# Ekran.net
KiCad netlist of a schematic drawn in EAGLE
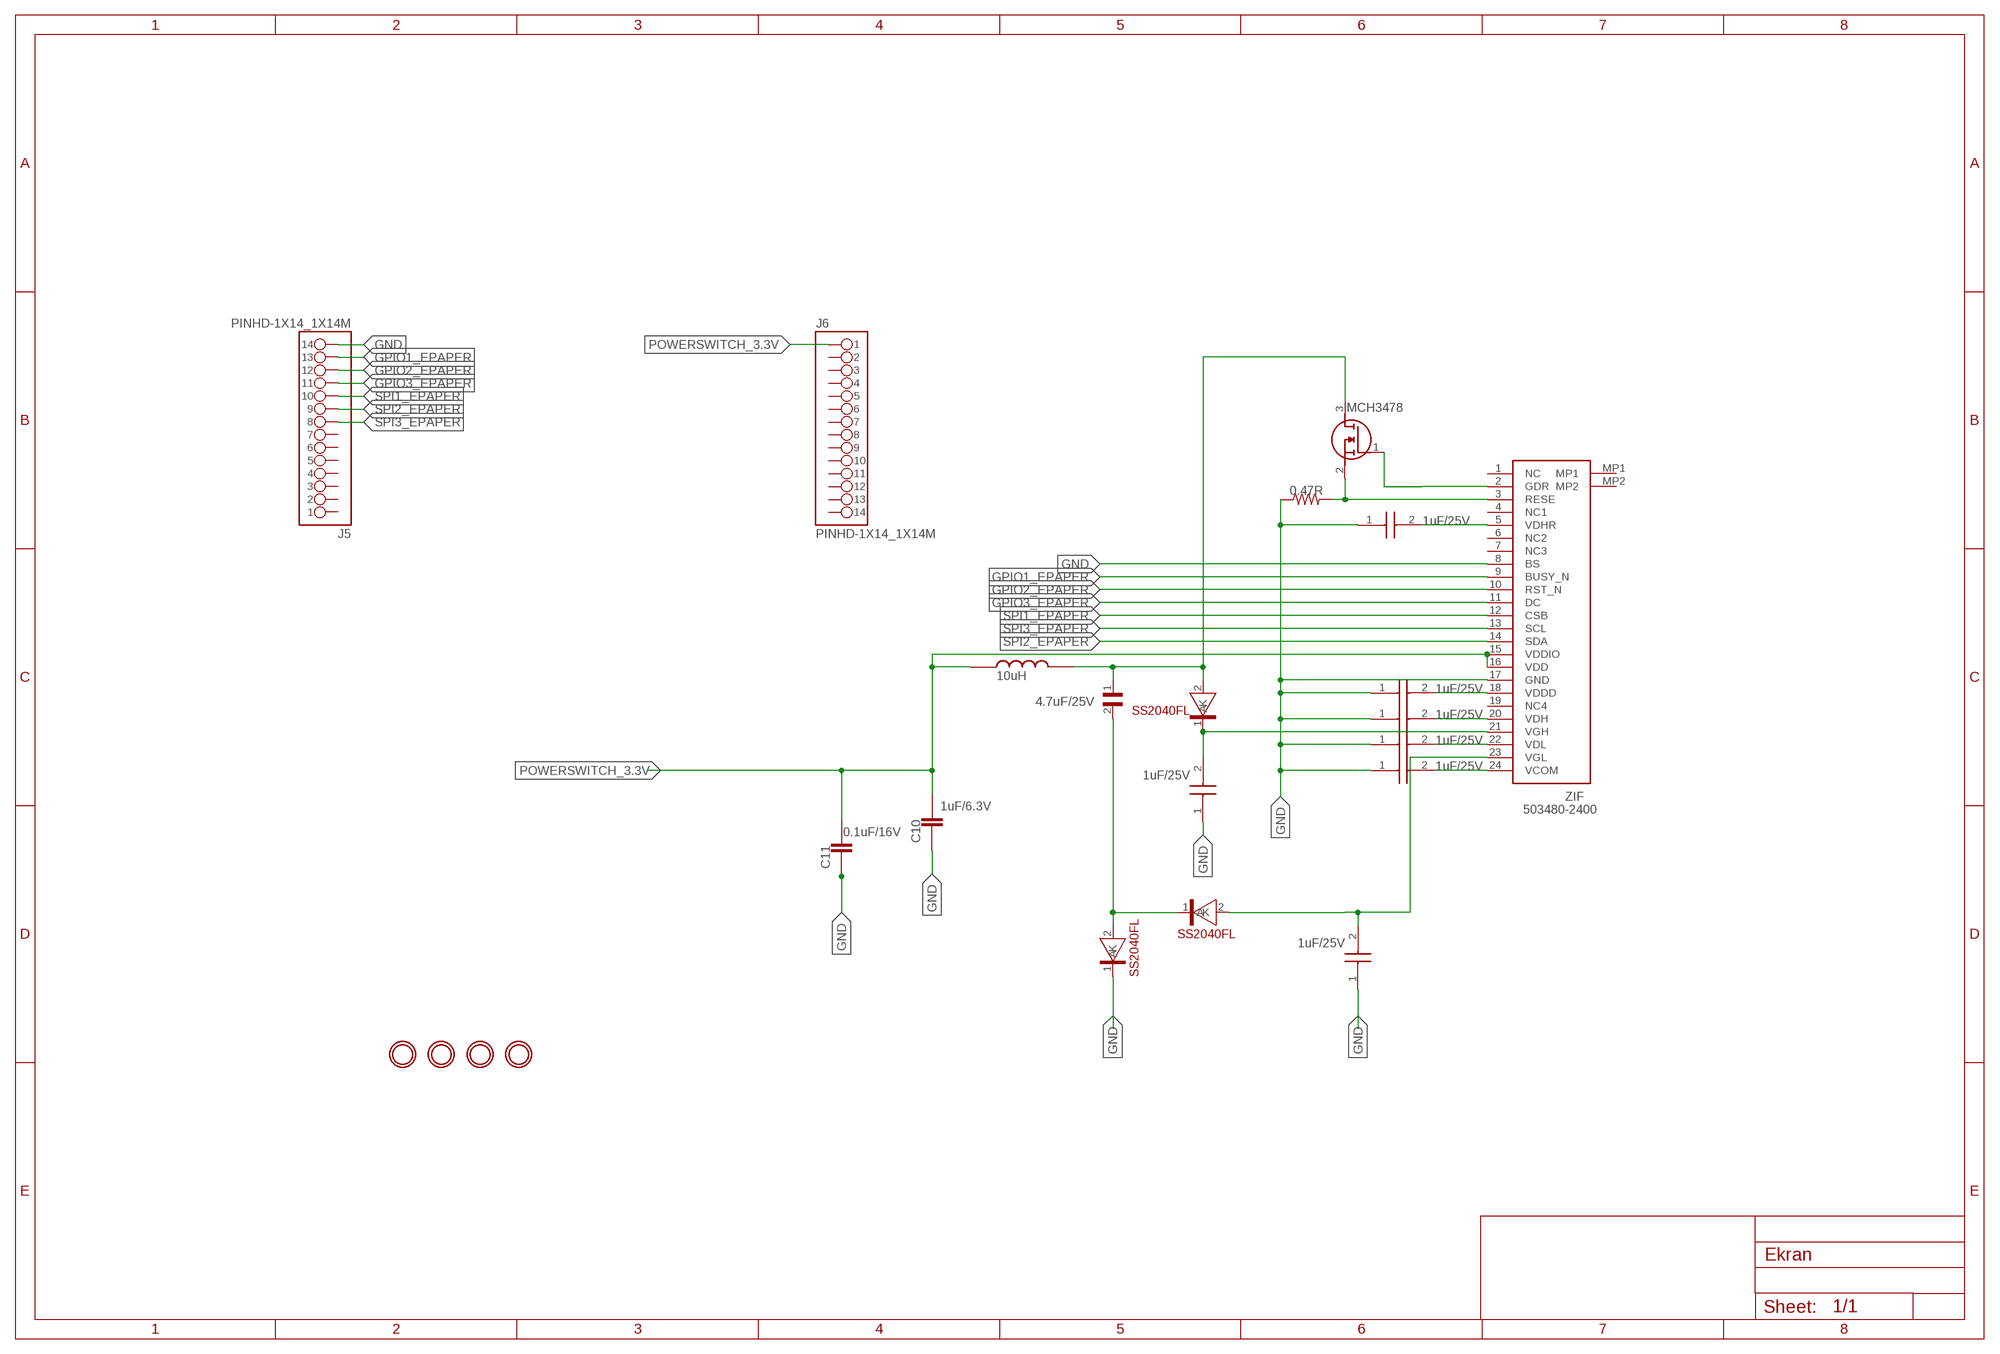
[diagram p0: schematic, sheet 1]

(export (version "E")
  (design (tool "Eeschema 10.0.6"))
  (components
    (comp (ref "C1")
      (value "MAJCT168BB7105KTEA01")
      (footprint "eagle-import:MAJX16")
      (description "1uF/25V")
      (libsource (lib "eagle-import") (part "MAJCT168BB7105KTEA01"))
    )
    (comp (ref "C2")
      (value "MAJCT168BB7105KTEA01")
      (footprint "eagle-import:MAJX16")
      (description "1uF/25V")
      (libsource (lib "eagle-import") (part "MAJCT168BB7105KTEA01"))
    )
    (comp (ref "C3")
      (value "MAJCT168BB7105KTEA01")
      (footprint "eagle-import:MAJX16")
      (description "1uF/25V")
      (libsource (lib "eagle-import") (part "MAJCT168BB7105KTEA01"))
    )
    (comp (ref "C4")
      (value "MAJCT168BB7105KTEA01")
      (footprint "eagle-import:MAJX16")
      (description "1uF/25V")
      (libsource (lib "eagle-import") (part "MAJCT168BB7105KTEA01"))
    )
    (comp (ref "C5")
      (value "MAJCT168BB7105KTEA01")
      (footprint "eagle-import:MAJX16")
      (description "1uF/25V")
      (libsource (lib "eagle-import") (part "MAJCT168BB7105KTEA01"))
    )
    (comp (ref "C6")
      (value "MAJCT168BB7105KTEA01")
      (footprint "eagle-import:MAJX16")
      (description "1uF/25V")
      (libsource (lib "eagle-import") (part "MAJCT168BB7105KTEA01"))
    )
    (comp (ref "C7")
      (value "4.7uF/25V")
      (footprint "eagle-import:CAPC3225X280N")
      (fields (field (name "MF") "KEMET") (field (name "MP") "C1210C475K3NACTU"))
      (libsource (lib "eagle-import") (part "C1210C475K3NACTU"))
    )
    (comp (ref "C8")
      (value "MAJCT168BB7105KTEA01")
      (footprint "eagle-import:MAJX16")
      (description "1uF/25V")
      (libsource (lib "eagle-import") (part "MAJCT168BB7105KTEA01"))
    )
    (comp (ref "C10")
      (value "1uF/6.3V")
      (footprint "eagle-import:CAPC1608X90")
      (fields (field (name "MF") "KYOCERA AVX") (field (name "MP") "06036D105KAT4A"))
      (libsource (lib "eagle-import") (part "06036D105KAT4A"))
    )
    (comp (ref "C11")
      (value "0.1uF/16V")
      (footprint "eagle-import:CAPC1608X90")
      (fields (field (name "MF") "KYOCERA AVX") (field (name "MP") "06036D105KAT4A"))
      (libsource (lib "eagle-import") (part "06036D105KAT4A"))
    )
    (comp (ref "J5")
      (value "PINHD-1X14_1X14M")
      (footprint "eagle-import:1X14")
      (libsource (lib "eagle-import") (part "PINHD-1X14_1X14M"))
    )
    (comp (ref "J6")
      (value "PINHD-1X14_1X14M")
      (footprint "eagle-import:1X14")
      (libsource (lib "eagle-import") (part "PINHD-1X14_1X14M"))
    )
    (comp (ref "L2")
      (value "10uH")
      (footprint "eagle-import:INDC1608X95N")
      (fields (field (name "MF") "Murata Electronics") (field (name "MP") "LQM18DN100M70L"))
      (libsource (lib "eagle-import") (part "LQM18DN100M70L"))
    )
    (comp (ref "Q1")
      (value "MCH3478")
      (footprint "eagle-import:SOTFL65P210X90-3N")
      (fields
        (field (name "MANUFACTURER_PART_NUMBER") "MCH3478-TL-W")
        (field (name "MOUSER_PART_NUMBER") "863-MCH3478-TL-W")
      )
      (libsource (lib "eagle-import") (part "MCH3478-TL-W"))
    )
    (comp (ref "R1")
      (value "0.47R")
      (footprint "eagle-import:RESAD724W46L381D178B")
      (libsource (lib "eagle-import") (part "R-USAXIAL-7.2MM-PITCH_"))
    )
    (comp (ref "U$1")
      (value "SS2040FL")
      (footprint "eagle-import:SOD-123FL")
      (fields (field (name "MF") "Panjit"))
      (libsource (lib "eagle-import") (part "SS2040FL"))
    )
    (comp (ref "U$2")
      (value "SS2040FL")
      (footprint "eagle-import:SOD-123FL")
      (fields (field (name "MF") "Panjit"))
      (libsource (lib "eagle-import") (part "SS2040FL"))
    )
    (comp (ref "U$3")
      (value "SS2040FL")
      (footprint "eagle-import:SOD-123FL")
      (fields (field (name "MF") "Panjit"))
      (libsource (lib "eagle-import") (part "SS2040FL"))
    )
    (comp (ref "U$4")
      (value "MOUNTINGHOLE2.5")
      (footprint "eagle-import:MOUNTINGHOLE_2.5_PLATED")
      (libsource (lib "eagle-import") (part "MOUNTINGHOLE2.5"))
    )
    (comp (ref "U$5")
      (value "MOUNTINGHOLE2.5")
      (footprint "eagle-import:MOUNTINGHOLE_2.5_PLATED")
      (libsource (lib "eagle-import") (part "MOUNTINGHOLE2.5"))
    )
    (comp (ref "U$6")
      (value "MOUNTINGHOLE2.5")
      (footprint "eagle-import:MOUNTINGHOLE_2.5_PLATED")
      (libsource (lib "eagle-import") (part "MOUNTINGHOLE2.5"))
    )
    (comp (ref "U$7")
      (value "MOUNTINGHOLE2.5")
      (footprint "eagle-import:MOUNTINGHOLE_2.5_PLATED")
      (libsource (lib "eagle-import") (part "MOUNTINGHOLE2.5"))
    )
    (comp (ref "ZIF")
      (value "503480-2400")
      (footprint "eagle-import:5034802400")
      (fields (field (name "MOUSER_PART_NUMBER") "538-503480-2400"))
      (libsource (lib "eagle-import") (part "503480-2400"))
    )
  )
  (nets
    (net (code "1") (name "GND") (class "Default")
      (node (ref "C1") (pin "1") (pinfunction "1_1") (pintype "bidirectional"))
      (node (ref "C10") (pin "1") (pinfunction "1_1") (pintype "passive"))
      (node (ref "C11") (pin "1") (pinfunction "1_1") (pintype "passive"))
      (node (ref "C2") (pin "1") (pinfunction "1_1") (pintype "bidirectional"))
      (node (ref "C3") (pin "1") (pinfunction "1_1") (pintype "bidirectional"))
      (node (ref "C4") (pin "1") (pinfunction "1_1") (pintype "bidirectional"))
      (node (ref "C5") (pin "1") (pinfunction "1_1") (pintype "bidirectional"))
      (node (ref "C6") (pin "1") (pinfunction "1_1") (pintype "bidirectional"))
      (node (ref "C8") (pin "1") (pinfunction "1_1") (pintype "bidirectional"))
      (node (ref "J5") (pin "14") (pinfunction "14_14") (pintype "bidirectional"))
      (node (ref "R1") (pin "1") (pinfunction "1_1") (pintype "passive"))
      (node (ref "U$2") (pin "1") (pinfunction "K_1") (pintype "passive"))
      (node (ref "ZIF") (pin "17") (pinfunction "GND_17") (pintype "bidirectional"))
      (node (ref "ZIF") (pin "8") (pinfunction "BS_8") (pintype "bidirectional"))
    )
    (net (code "2") (name "GPIO1_EPAPER") (class "Default")
      (node (ref "J5") (pin "13") (pinfunction "13_13") (pintype "bidirectional"))
      (node (ref "ZIF") (pin "9") (pinfunction "BUSY_N_9") (pintype "bidirectional"))
    )
    (net (code "3") (name "GPIO2_EPAPER") (class "Default")
      (node (ref "J5") (pin "12") (pinfunction "12_12") (pintype "bidirectional"))
      (node (ref "ZIF") (pin "10") (pinfunction "RST_N_10") (pintype "bidirectional"))
    )
    (net (code "4") (name "GPIO3_EPAPER") (class "Default")
      (node (ref "J5") (pin "11") (pinfunction "11_11") (pintype "bidirectional"))
      (node (ref "ZIF") (pin "11") (pinfunction "DC_11") (pintype "bidirectional"))
    )
    (net (code "5") (name "Net-(Q1-D)") (class "Default")
      (node (ref "C7") (pin "1") (pinfunction "1_1") (pintype "passive"))
      (node (ref "L2") (pin "2") (pinfunction "2_2") (pintype "passive"))
      (node (ref "Q1") (pin "3") (pinfunction "D_3") (pintype "bidirectional"))
      (node (ref "U$1") (pin "2") (pinfunction "A_2") (pintype "passive"))
    )
    (net (code "6") (name "Net-(Q1-G)") (class "Default")
      (node (ref "Q1") (pin "1") (pinfunction "G_1") (pintype "bidirectional"))
      (node (ref "ZIF") (pin "2") (pinfunction "GDR_2") (pintype "bidirectional"))
    )
    (net (code "7") (name "Net-(Q1-S)") (class "Default")
      (node (ref "Q1") (pin "2") (pinfunction "S_2") (pintype "bidirectional"))
      (node (ref "R1") (pin "2") (pinfunction "2_2") (pintype "passive"))
      (node (ref "ZIF") (pin "3") (pinfunction "RESE_3") (pintype "bidirectional"))
    )
    (net (code "8") (name "Net-(U$1-K)") (class "Default")
      (node (ref "C6") (pin "2") (pinfunction "2_2") (pintype "bidirectional"))
      (node (ref "U$1") (pin "1") (pinfunction "K_1") (pintype "passive"))
      (node (ref "ZIF") (pin "21") (pinfunction "VGH_21") (pintype "bidirectional"))
    )
    (net (code "9") (name "Net-(U$2-A)") (class "Default")
      (node (ref "C7") (pin "2") (pinfunction "2_2") (pintype "passive"))
      (node (ref "U$2") (pin "2") (pinfunction "A_2") (pintype "passive"))
      (node (ref "U$3") (pin "1") (pinfunction "K_1") (pintype "passive"))
    )
    (net (code "10") (name "Net-(U$3-A)") (class "Default")
      (node (ref "C8") (pin "2") (pinfunction "2_2") (pintype "bidirectional"))
      (node (ref "U$3") (pin "2") (pinfunction "A_2") (pintype "passive"))
      (node (ref "ZIF") (pin "23") (pinfunction "VGL_23") (pintype "bidirectional"))
    )
    (net (code "11") (name "Net-(ZIF-VCOM)") (class "Default")
      (node (ref "C3") (pin "2") (pinfunction "2_2") (pintype "bidirectional"))
      (node (ref "ZIF") (pin "24") (pinfunction "VCOM_24") (pintype "bidirectional"))
    )
    (net (code "12") (name "Net-(ZIF-VDDD)") (class "Default")
      (node (ref "C4") (pin "2") (pinfunction "2_2") (pintype "bidirectional"))
      (node (ref "ZIF") (pin "18") (pinfunction "VDDD_18") (pintype "bidirectional"))
    )
    (net (code "13") (name "Net-(ZIF-VDH)") (class "Default")
      (node (ref "C1") (pin "2") (pinfunction "2_2") (pintype "bidirectional"))
      (node (ref "ZIF") (pin "20") (pinfunction "VDH_20") (pintype "bidirectional"))
    )
    (net (code "14") (name "Net-(ZIF-VDHR)") (class "Default")
      (node (ref "C5") (pin "2") (pinfunction "2_2") (pintype "bidirectional"))
      (node (ref "ZIF") (pin "5") (pinfunction "VDHR_5") (pintype "bidirectional"))
    )
    (net (code "15") (name "Net-(ZIF-VDL)") (class "Default")
      (node (ref "C2") (pin "2") (pinfunction "2_2") (pintype "bidirectional"))
      (node (ref "ZIF") (pin "22") (pinfunction "VDL_22") (pintype "bidirectional"))
    )
    (net (code "16") (name "POWERSWITCH_3.3V") (class "Default")
      (node (ref "C10") (pin "2") (pinfunction "2_2") (pintype "passive"))
      (node (ref "C11") (pin "2") (pinfunction "2_2") (pintype "passive"))
      (node (ref "J6") (pin "1") (pinfunction "1_1") (pintype "bidirectional"))
      (node (ref "L2") (pin "1") (pinfunction "1_1") (pintype "passive"))
      (node (ref "ZIF") (pin "15") (pinfunction "VDDIO_15") (pintype "bidirectional"))
      (node (ref "ZIF") (pin "16") (pinfunction "VDD_16") (pintype "bidirectional"))
    )
    (net (code "17") (name "SPI1_EPAPER") (class "Default")
      (node (ref "J5") (pin "10") (pinfunction "10_10") (pintype "bidirectional"))
      (node (ref "ZIF") (pin "12") (pinfunction "CSB_12") (pintype "bidirectional"))
    )
    (net (code "18") (name "SPI2_EPAPER") (class "Default")
      (node (ref "J5") (pin "9") (pinfunction "9_9") (pintype "bidirectional"))
      (node (ref "ZIF") (pin "14") (pinfunction "SDA_14") (pintype "bidirectional"))
    )
    (net (code "19") (name "SPI3_EPAPER") (class "Default")
      (node (ref "J5") (pin "8") (pinfunction "8_8") (pintype "bidirectional"))
      (node (ref "ZIF") (pin "13") (pinfunction "SCL_13") (pintype "bidirectional"))
    )
    (net (code "20") (name "unconnected-(J5-Pad1)") (class "Default")
      (node (ref "J5") (pin "1") (pinfunction "1_1") (pintype "bidirectional"))
    )
    (net (code "21") (name "unconnected-(J5-Pad2)") (class "Default")
      (node (ref "J5") (pin "2") (pinfunction "2_2") (pintype "bidirectional"))
    )
    (net (code "22") (name "unconnected-(J5-Pad3)") (class "Default")
      (node (ref "J5") (pin "3") (pinfunction "3_3") (pintype "bidirectional"))
    )
    (net (code "23") (name "unconnected-(J5-Pad4)") (class "Default")
      (node (ref "J5") (pin "4") (pinfunction "4_4") (pintype "bidirectional"))
    )
    (net (code "24") (name "unconnected-(J5-Pad5)") (class "Default")
      (node (ref "J5") (pin "5") (pinfunction "5_5") (pintype "bidirectional"))
    )
    (net (code "25") (name "unconnected-(J5-Pad6)") (class "Default")
      (node (ref "J5") (pin "6") (pinfunction "6_6") (pintype "bidirectional"))
    )
    (net (code "26") (name "unconnected-(J5-Pad7)") (class "Default")
      (node (ref "J5") (pin "7") (pinfunction "7_7") (pintype "bidirectional"))
    )
    (net (code "27") (name "unconnected-(J6-Pad2)") (class "Default")
      (node (ref "J6") (pin "2") (pinfunction "2_2") (pintype "bidirectional"))
    )
    (net (code "28") (name "unconnected-(J6-Pad3)") (class "Default")
      (node (ref "J6") (pin "3") (pinfunction "3_3") (pintype "bidirectional"))
    )
    (net (code "29") (name "unconnected-(J6-Pad4)") (class "Default")
      (node (ref "J6") (pin "4") (pinfunction "4_4") (pintype "bidirectional"))
    )
    (net (code "30") (name "unconnected-(J6-Pad5)") (class "Default")
      (node (ref "J6") (pin "5") (pinfunction "5_5") (pintype "bidirectional"))
    )
    (net (code "31") (name "unconnected-(J6-Pad6)") (class "Default")
      (node (ref "J6") (pin "6") (pinfunction "6_6") (pintype "bidirectional"))
    )
    (net (code "32") (name "unconnected-(J6-Pad7)") (class "Default")
      (node (ref "J6") (pin "7") (pinfunction "7_7") (pintype "bidirectional"))
    )
    (net (code "33") (name "unconnected-(J6-Pad8)") (class "Default")
      (node (ref "J6") (pin "8") (pinfunction "8_8") (pintype "bidirectional"))
    )
    (net (code "34") (name "unconnected-(J6-Pad9)") (class "Default")
      (node (ref "J6") (pin "9") (pinfunction "9_9") (pintype "bidirectional"))
    )
    (net (code "35") (name "unconnected-(J6-Pad10)") (class "Default")
      (node (ref "J6") (pin "10") (pinfunction "10_10") (pintype "bidirectional"))
    )
    (net (code "36") (name "unconnected-(J6-Pad11)") (class "Default")
      (node (ref "J6") (pin "11") (pinfunction "11_11") (pintype "bidirectional"))
    )
    (net (code "37") (name "unconnected-(J6-Pad12)") (class "Default")
      (node (ref "J6") (pin "12") (pinfunction "12_12") (pintype "bidirectional"))
    )
    (net (code "38") (name "unconnected-(J6-Pad13)") (class "Default")
      (node (ref "J6") (pin "13") (pinfunction "13_13") (pintype "bidirectional"))
    )
    (net (code "39") (name "unconnected-(J6-Pad14)") (class "Default")
      (node (ref "J6") (pin "14") (pinfunction "14_14") (pintype "bidirectional"))
    )
    (net (code "40") (name "unconnected-(ZIF-NC-Pad1)") (class "Default")
      (node (ref "ZIF") (pin "1") (pinfunction "NC_1") (pintype "bidirectional"))
    )
    (net (code "41") (name "unconnected-(ZIF-NC1-Pad4)") (class "Default")
      (node (ref "ZIF") (pin "4") (pinfunction "NC1_4") (pintype "bidirectional"))
    )
    (net (code "42") (name "unconnected-(ZIF-NC2-Pad6)") (class "Default")
      (node (ref "ZIF") (pin "6") (pinfunction "NC2_6") (pintype "bidirectional"))
    )
    (net (code "43") (name "unconnected-(ZIF-NC3-Pad7)") (class "Default")
      (node (ref "ZIF") (pin "7") (pinfunction "NC3_7") (pintype "bidirectional"))
    )
    (net (code "44") (name "unconnected-(ZIF-NC4-Pad19)") (class "Default")
      (node (ref "ZIF") (pin "19") (pinfunction "NC4_19") (pintype "bidirectional"))
    )
    (net (code "45") (name "unconnected-(ZIF-PadMP1)") (class "Default")
      (node (ref "ZIF") (pin "MP1") (pinfunction "MP1_MP1") (pintype "bidirectional"))
    )
    (net (code "46") (name "unconnected-(ZIF-PadMP2)") (class "Default")
      (node (ref "ZIF") (pin "MP2") (pinfunction "MP2_MP2") (pintype "bidirectional"))
    )
  )
)
